# box.net
KiCad netlist of a schematic drawn in EAGLE
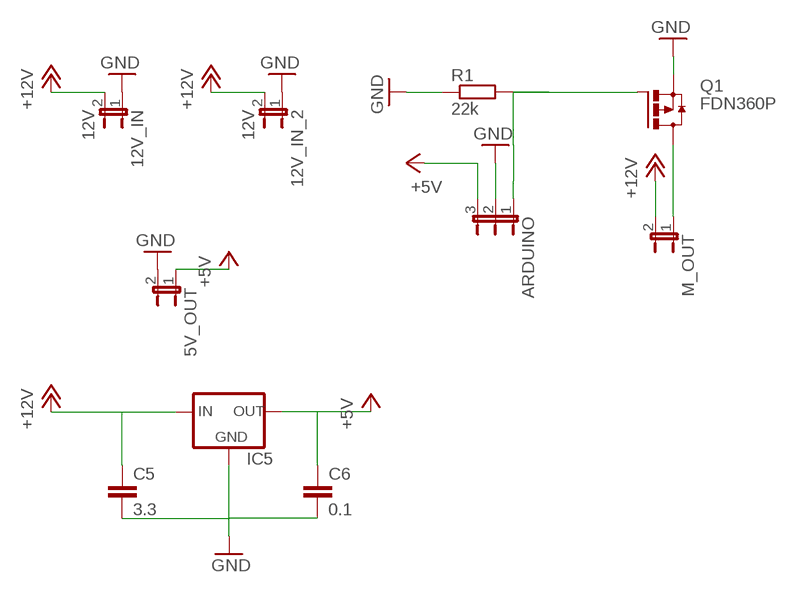
[diagram p0: schematic, sheet 1]

(export (version "E")
  (design (tool "Eeschema 10.0.6"))
  (components
    (comp (ref "5V_OUT")
      (value "JP1E")
      (footprint "eagle-import:JP1")
      (libsource (lib "eagle-import") (part "JP1E"))
    )
    (comp (ref "12V_IN")
      (value "12V")
      (footprint "eagle-import:JP1")
      (libsource (lib "eagle-import") (part "JP1E"))
    )
    (comp (ref "12V_IN_2")
      (value "12V")
      (footprint "eagle-import:JP1")
      (libsource (lib "eagle-import") (part "JP1E"))
    )
    (comp (ref "ARDUINO")
      (value "JP2E")
      (footprint "eagle-import:JP2")
      (libsource (lib "eagle-import") (part "JP2E"))
    )
    (comp (ref "C5")
      (value "3.3")
      (footprint "eagle-import:C025-024X044")
      (libsource (lib "eagle-import") (part "C-EU025-024X044"))
    )
    (comp (ref "C6")
      (value "0.1")
      (footprint "eagle-import:C025-024X044")
      (libsource (lib "eagle-import") (part "C-EU025-024X044"))
    )
    (comp (ref "IC5")
      (value "78XXL")
      (footprint "eagle-import:78XXL")
      (libsource (lib "eagle-import") (part "78XXL"))
    )
    (comp (ref "M_OUT")
      (value "JP1E")
      (footprint "eagle-import:JP1")
      (libsource (lib "eagle-import") (part "JP1E"))
    )
    (comp (ref "Q1")
      (value "FDN360P")
      (footprint "eagle-import:SUPER-SOT3")
      (libsource (lib "eagle-import") (part "FDN360P"))
    )
    (comp (ref "R1")
      (value "22k")
      (footprint "eagle-import:0204_7")
      (libsource (lib "eagle-import") (part "R-EU_0204/7"))
    )
  )
  (nets
    (net (code "1") (name "+5V") (class "Default")
      (node (ref "5V_OUT") (pin "1") (pinfunction "1_1") (pintype "passive"))
      (node (ref "ARDUINO") (pin "3") (pinfunction "3_3") (pintype "passive"))
      (node (ref "C6") (pin "1") (pinfunction "1_1") (pintype "passive"))
      (node (ref "IC5") (pin "OUT") (pinfunction "OUT_OUT") (pintype "passive"))
    )
    (net (code "2") (name "+12V") (class "Default")
      (node (ref "12V_IN") (pin "2") (pinfunction "2_2") (pintype "passive"))
      (node (ref "12V_IN_2") (pin "2") (pinfunction "2_2") (pintype "passive"))
      (node (ref "C5") (pin "1") (pinfunction "1_1") (pintype "passive"))
      (node (ref "IC5") (pin "IN") (pinfunction "IN_IN") (pintype "input"))
      (node (ref "M_OUT") (pin "2") (pinfunction "2_2") (pintype "passive"))
    )
    (net (code "3") (name "GND") (class "Default")
      (node (ref "12V_IN") (pin "1") (pinfunction "1_1") (pintype "passive"))
      (node (ref "12V_IN_2") (pin "1") (pinfunction "1_1") (pintype "passive"))
      (node (ref "5V_OUT") (pin "2") (pinfunction "2_2") (pintype "passive"))
      (node (ref "ARDUINO") (pin "2") (pinfunction "2_2") (pintype "passive"))
      (node (ref "C5") (pin "2") (pinfunction "2_2") (pintype "passive"))
      (node (ref "C6") (pin "2") (pinfunction "2_2") (pintype "passive"))
      (node (ref "IC5") (pin "GND") (pinfunction "GND_GND") (pintype "input"))
      (node (ref "Q1") (pin "2") (pinfunction "S_2") (pintype "passive"))
      (node (ref "R1") (pin "1") (pinfunction "1_1") (pintype "passive"))
    )
    (net (code "4") (name "Net-(Q1-D)") (class "Default")
      (node (ref "M_OUT") (pin "1") (pinfunction "1_1") (pintype "passive"))
      (node (ref "Q1") (pin "3") (pinfunction "D_3") (pintype "passive"))
    )
    (net (code "5") (name "Net-(Q1-G)") (class "Default")
      (node (ref "ARDUINO") (pin "1") (pinfunction "1_1") (pintype "passive"))
      (node (ref "Q1") (pin "1") (pinfunction "G_1") (pintype "passive"))
      (node (ref "R1") (pin "2") (pinfunction "2_2") (pintype "passive"))
    )
  )
)
